# 485_CommunicactionInterface.net
KiCad netlist of a schematic drawn in Altium Designer
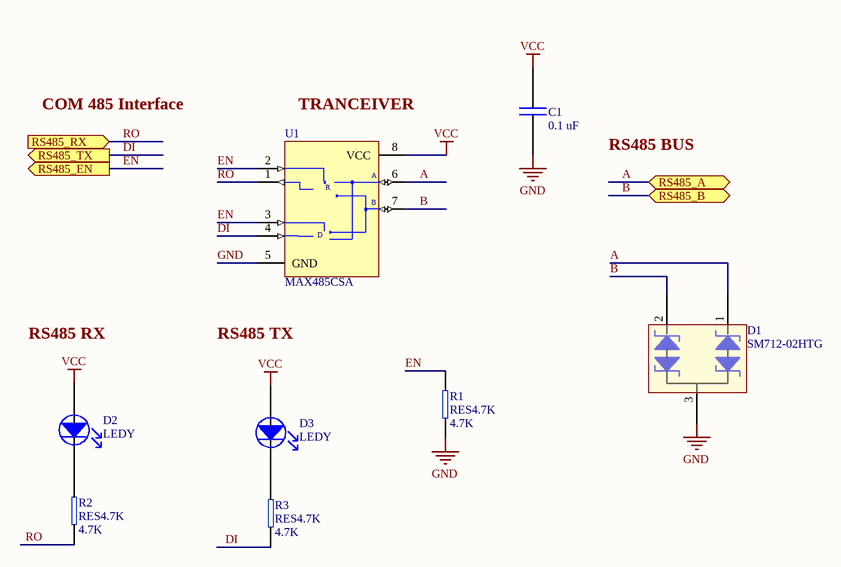
[diagram p0: 485_CommunicactionInterface.SchDoc]

(export (version "E")
  (design (tool "Eeschema 10.0.6"))
  (components
    (comp (ref "C1")
      (value "0.1 uF")
      (footprint "techdev:CAP0603")
      (description "Capacitores cerámicos de capas múltiples (MLCC) - SMD/SMT 0603 0.1uF 16volts X7R 5%")
      (fields (field (name "MPN") "VJ0603Y104JXJPW1BC") (field (name "Comment") "CAP0.1uF"))
      (libsource (lib "Miscellaneous Devices") (part "C0.1UF"))
    )
    (comp (ref "D1")
      (value "SM712-02HTG")
      (footprint "SW712")
      (description "Secuencias de diodos de TVS 600W 2 Channel Green Asymmetrical SOT23-3 (- 7 V to + 12 V)")
      (libsource (lib "Miscellaneous Devices") (part "SM712-02HTG"))
    )
    (comp (ref "D2")
      (value "LEDY")
      (footprint "150060YS75000")
      (description "LED estándar - SMD (montaje superficial) WL-SMCW SMDMono TpVw Waterclr 0603 Yellow")
      (fields (field (name "MPN") "150060YS75000"))
      (libsource (lib "techdev") (part "LEDY"))
    )
    (comp (ref "D3")
      (value "LEDY")
      (footprint "150060YS75000")
      (description "LED estándar - SMD (montaje superficial) WL-SMCW SMDMono TpVw Waterclr 0603 Yellow")
      (fields (field (name "MPN") "150060YS75000"))
      (libsource (lib "techdev") (part "LEDY"))
    )
    (comp (ref "R1")
      (value "RES4.7K")
      (footprint "RES0603")
      (description "Resistores de película gruesa - SMD 1/10watt 4.7Kohms 1%")
      (fields (field (name "MPN") "CRCW06034K70FKEA") (field (name "ALTIUM_VALUE") "4.7K"))
      (libsource (lib "Miscellaneous Devices") (part "RES4.7K"))
    )
    (comp (ref "R2")
      (value "RES4.7K")
      (footprint "RES0603")
      (description "Resistores de película gruesa - SMD 1/10watt 4.7Kohms 1%")
      (fields (field (name "MPN") "CRCW06034K70FKEA") (field (name "ALTIUM_VALUE") "4.7K"))
      (libsource (lib "Miscellaneous Devices") (part "RES4.7K"))
    )
    (comp (ref "R3")
      (value "RES4.7K")
      (footprint "RES0603")
      (description "Resistores de película gruesa - SMD 1/10watt 4.7Kohms 1%")
      (fields (field (name "MPN") "CRCW06034K70FKEA") (field (name "ALTIUM_VALUE") "4.7K"))
      (libsource (lib "Miscellaneous Devices") (part "RES4.7K"))
    )
    (comp (ref "U1")
      (value "MAX485CSA")
      (footprint "NSO8_N")
      (description "Low-Power, Slew-Rate-Limited RS-485/RS-422 Transceiver")
      (fields (field (name "MPN") "MAX485CSA+"))
      (libsource (lib "Maxim Communication Transceiver") (part "MAX485CSA"))
    )
  )
  (nets
    (net (code "1") (name "/A") (class "Default")
      (node (ref "D1") (pin "1") (pinfunction "1_1") (pintype "passive"))
      (node (ref "U1") (pin "6") (pinfunction "A_6") (pintype "bidirectional"))
    )
    (net (code "2") (name "/B") (class "Default")
      (node (ref "D1") (pin "2") (pinfunction "2_2") (pintype "passive"))
      (node (ref "U1") (pin "7") (pinfunction "B_7") (pintype "bidirectional"))
    )
    (net (code "4") (name "/DI") (class "Default")
      (node (ref "R3") (pin "2") (pinfunction "neg_2") (pintype "passive"))
      (node (ref "U1") (pin "4") (pinfunction "DI_4") (pintype "input"))
    )
    (net (code "5") (name "/EN") (class "Default")
      (node (ref "R1") (pin "1") (pinfunction "pos_1") (pintype "passive"))
      (node (ref "U1") (pin "2") (pinfunction "~{RE}_2") (pintype "input"))
      (node (ref "U1") (pin "3") (pinfunction "DE_3") (pintype "input"))
    )
    (net (code "6") (name "/RO") (class "Default")
      (node (ref "R2") (pin "2") (pinfunction "neg_2") (pintype "passive"))
      (node (ref "U1") (pin "1") (pinfunction "RO_1") (pintype "output"))
    )
    (net (code "11") (name "GND") (class "Default")
      (node (ref "C1") (pin "2") (pintype "passive"))
      (node (ref "D1") (pin "3") (pinfunction "3_3") (pintype "passive"))
      (node (ref "R1") (pin "2") (pinfunction "neg_2") (pintype "passive"))
      (node (ref "U1") (pin "5") (pinfunction "GND_5") (pintype "power_in"))
    )
    (net (code "12") (name "Net-(D2-Cathode)") (class "Default")
      (node (ref "D2") (pin "1") (pinfunction "Cathode_1") (pintype "passive"))
      (node (ref "R2") (pin "1") (pinfunction "pos_1") (pintype "passive"))
    )
    (net (code "13") (name "Net-(D3-Cathode)") (class "Default")
      (node (ref "D3") (pin "1") (pinfunction "Cathode_1") (pintype "passive"))
      (node (ref "R3") (pin "1") (pinfunction "pos_1") (pintype "passive"))
    )
    (net (code "14") (name "VCC") (class "Default")
      (node (ref "C1") (pin "1") (pintype "passive"))
      (node (ref "D2") (pin "2") (pinfunction "Anode_2") (pintype "passive"))
      (node (ref "D3") (pin "2") (pinfunction "Anode_2") (pintype "passive"))
      (node (ref "U1") (pin "8") (pinfunction "VCC_8") (pintype "power_in"))
    )
  )
)
